# PBC-1.net
KiCad netlist of a schematic drawn in EAGLE
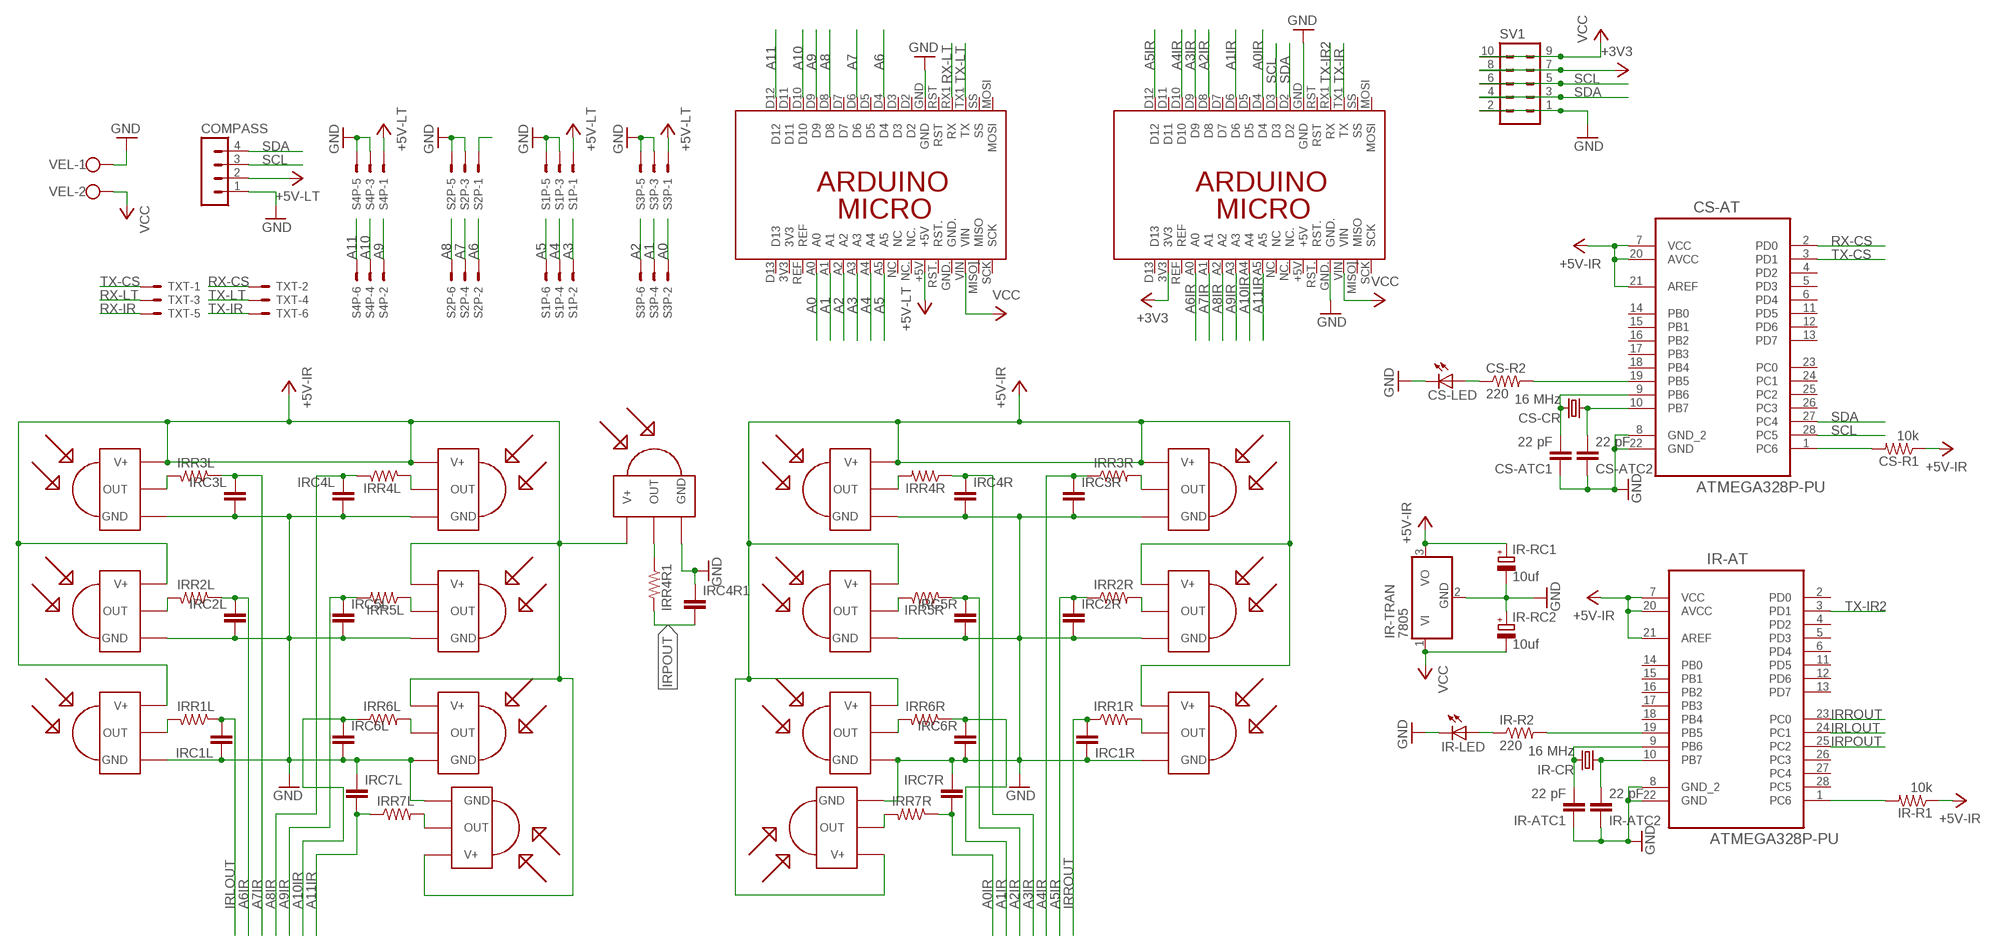
[diagram p0: schematic, sheet 1]

(export (version "E")
  (design (tool "Eeschema 10.0.6"))
  (components
    (comp (ref "COMPASS")
      (value "MA04-1")
      (footprint "eagle-import:MA04-1")
      (libsource (lib "eagle-import") (part "MA04-1"))
    )
    (comp (ref "CS-AT")
      (value "ATMEGA328P-PU")
      (footprint "eagle-import:DIP254P762X457-28")
      (libsource (lib "eagle-import") (part "ATMEGA328P-PU"))
    )
    (comp (ref "CS-ATC1")
      (value "22 pF")
      (footprint "eagle-import:C025-024X044")
      (libsource (lib "eagle-import") (part "C-EU025-024X044"))
    )
    (comp (ref "CS-ATC2")
      (value "22 pF")
      (footprint "eagle-import:C025-024X044")
      (libsource (lib "eagle-import") (part "C-EU025-024X044"))
    )
    (comp (ref "CS-CR")
      (value "16 MHz")
      (footprint "eagle-import:HC49U70")
      (libsource (lib "eagle-import") (part "CRYSTALHC49U70"))
    )
    (comp (ref "CS-LED")
      (value "LED5MM")
      (footprint "eagle-import:LED5MM")
      (libsource (lib "eagle-import") (part "LED5MM"))
    )
    (comp (ref "CS-R1")
      (value "10k")
      (footprint "eagle-import:0204_7")
      (libsource (lib "eagle-import") (part "R-US_0204/7"))
    )
    (comp (ref "CS-R2")
      (value "220")
      (footprint "eagle-import:0204_7")
      (libsource (lib "eagle-import") (part "R-US_0204/7"))
    )
    (comp (ref "IR-AT")
      (value "ATMEGA328P-PU")
      (footprint "eagle-import:DIP254P762X457-28")
      (libsource (lib "eagle-import") (part "ATMEGA328P-PU"))
    )
    (comp (ref "IR-ATC1")
      (value "22 pF")
      (footprint "eagle-import:C025-024X044")
      (libsource (lib "eagle-import") (part "C-EU025-024X044"))
    )
    (comp (ref "IR-ATC2")
      (value "22 pF")
      (footprint "eagle-import:C025-024X044")
      (libsource (lib "eagle-import") (part "C-EU025-024X044"))
    )
    (comp (ref "IR-CR")
      (value "16 MHz")
      (footprint "eagle-import:HC49U70")
      (libsource (lib "eagle-import") (part "CRYSTALHC49U70"))
    )
    (comp (ref "IR-LED")
      (value "LED5MM")
      (footprint "eagle-import:LED5MM")
      (libsource (lib "eagle-import") (part "LED5MM"))
    )
    (comp (ref "IR-R1")
      (value "10k")
      (footprint "eagle-import:0204_7")
      (libsource (lib "eagle-import") (part "R-US_0204/7"))
    )
    (comp (ref "IR-R2")
      (value "220")
      (footprint "eagle-import:0204_7")
      (libsource (lib "eagle-import") (part "R-US_0204/7"))
    )
    (comp (ref "IR-RC1")
      (value "10uf")
      (footprint "eagle-import:TT2D5")
      (libsource (lib "eagle-import") (part "CPOL-EUTT2D5"))
    )
    (comp (ref "IR-RC2")
      (value "10uf")
      (footprint "eagle-import:TT2D5")
      (libsource (lib "eagle-import") (part "CPOL-EUTT2D5"))
    )
    (comp (ref "IR-TRAN")
      (value "7805")
      (footprint "eagle-import:TO220H")
      (libsource (lib "eagle-import") (part "78T05"))
    )
    (comp (ref "IRC1L")
      (value "C-EU025-024X044")
      (footprint "eagle-import:C025-024X044")
      (libsource (lib "eagle-import") (part "C-EU025-024X044"))
    )
    (comp (ref "IRC1R")
      (value "C-EU025-024X044")
      (footprint "eagle-import:C025-024X044")
      (libsource (lib "eagle-import") (part "C-EU025-024X044"))
    )
    (comp (ref "IRC2L")
      (value "C-EU025-024X044")
      (footprint "eagle-import:C025-024X044")
      (libsource (lib "eagle-import") (part "C-EU025-024X044"))
    )
    (comp (ref "IRC2R")
      (value "C-EU025-024X044")
      (footprint "eagle-import:C025-024X044")
      (libsource (lib "eagle-import") (part "C-EU025-024X044"))
    )
    (comp (ref "IRC3L")
      (value "C-EU025-024X044")
      (footprint "eagle-import:C025-024X044")
      (libsource (lib "eagle-import") (part "C-EU025-024X044"))
    )
    (comp (ref "IRC3R")
      (value "C-EU025-024X044")
      (footprint "eagle-import:C025-024X044")
      (libsource (lib "eagle-import") (part "C-EU025-024X044"))
    )
    (comp (ref "IRC4L")
      (value "C-EU025-024X044")
      (footprint "eagle-import:C025-024X044")
      (libsource (lib "eagle-import") (part "C-EU025-024X044"))
    )
    (comp (ref "IRC4R")
      (value "C-EU025-024X044")
      (footprint "eagle-import:C025-024X044")
      (libsource (lib "eagle-import") (part "C-EU025-024X044"))
    )
    (comp (ref "IRC4R1")
      (value "C-EU025-024X044")
      (footprint "eagle-import:C025-024X044")
      (libsource (lib "eagle-import") (part "C-EU025-024X044"))
    )
    (comp (ref "IRC5L")
      (value "C-EU025-024X044")
      (footprint "eagle-import:C025-024X044")
      (libsource (lib "eagle-import") (part "C-EU025-024X044"))
    )
    (comp (ref "IRC5R")
      (value "C-EU025-024X044")
      (footprint "eagle-import:C025-024X044")
      (libsource (lib "eagle-import") (part "C-EU025-024X044"))
    )
    (comp (ref "IRC6L")
      (value "C-EU025-024X044")
      (footprint "eagle-import:C025-024X044")
      (libsource (lib "eagle-import") (part "C-EU025-024X044"))
    )
    (comp (ref "IRC6R")
      (value "C-EU025-024X044")
      (footprint "eagle-import:C025-024X044")
      (libsource (lib "eagle-import") (part "C-EU025-024X044"))
    )
    (comp (ref "IRC7L")
      (value "C-EU025-024X044")
      (footprint "eagle-import:C025-024X044")
      (libsource (lib "eagle-import") (part "C-EU025-024X044"))
    )
    (comp (ref "IRC7R")
      (value "C-EU025-024X044")
      (footprint "eagle-import:C025-024X044")
      (libsource (lib "eagle-import") (part "C-EU025-024X044"))
    )
    (comp (ref "IRD1L")
      (value "TSOP2240")
      (footprint "eagle-import:TSOP18XX")
      (libsource (lib "eagle-import") (part "TSOP1840"))
    )
    (comp (ref "IRD1R")
      (value "TSOP2240")
      (footprint "eagle-import:TSOP18XX")
      (libsource (lib "eagle-import") (part "TSOP1840"))
    )
    (comp (ref "IRD2L")
      (value "TSOP2240")
      (footprint "eagle-import:TSOP18XX")
      (libsource (lib "eagle-import") (part "TSOP1840"))
    )
    (comp (ref "IRD2R")
      (value "TSOP2240")
      (footprint "eagle-import:TSOP18XX")
      (libsource (lib "eagle-import") (part "TSOP1840"))
    )
    (comp (ref "IRD3L")
      (value "TSOP2240")
      (footprint "eagle-import:TSOP18XX")
      (libsource (lib "eagle-import") (part "TSOP1840"))
    )
    (comp (ref "IRD3R")
      (value "TSOP1840")
      (footprint "eagle-import:TSOP18XX")
      (libsource (lib "eagle-import") (part "TSOP1840"))
    )
    (comp (ref "IRD4L")
      (value "TSOP2240")
      (footprint "eagle-import:TSOP18XX")
      (libsource (lib "eagle-import") (part "TSOP1840"))
    )
    (comp (ref "IRD4R")
      (value "TSOP2240")
      (footprint "eagle-import:TSOP18XX")
      (libsource (lib "eagle-import") (part "TSOP1840"))
    )
    (comp (ref "IRD5L")
      (value "TSOP2240")
      (footprint "eagle-import:TSOP18XX")
      (libsource (lib "eagle-import") (part "TSOP1840"))
    )
    (comp (ref "IRD5R")
      (value "TSOP2240")
      (footprint "eagle-import:TSOP18XX")
      (libsource (lib "eagle-import") (part "TSOP1840"))
    )
    (comp (ref "IRD6L")
      (value "TSOP2240")
      (footprint "eagle-import:TSOP18XX")
      (libsource (lib "eagle-import") (part "TSOP1840"))
    )
    (comp (ref "IRD6R")
      (value "TSOP2240")
      (footprint "eagle-import:TSOP18XX")
      (libsource (lib "eagle-import") (part "TSOP1840"))
    )
    (comp (ref "IRD7L")
      (value "TSOP2240")
      (footprint "eagle-import:TSOP18XX")
      (libsource (lib "eagle-import") (part "TSOP1840"))
    )
    (comp (ref "IRD7R")
      (value "TSOP2240")
      (footprint "eagle-import:TSOP18XX")
      (libsource (lib "eagle-import") (part "TSOP1840"))
    )
    (comp (ref "IRDP")
      (value "TSOP2240")
      (footprint "eagle-import:TSOP18XX")
      (libsource (lib "eagle-import") (part "TSOP1840"))
    )
    (comp (ref "IRR1L")
      (value "R-US_0204/5")
      (footprint "eagle-import:0204_5")
      (libsource (lib "eagle-import") (part "R-US_0204/5"))
    )
    (comp (ref "IRR1R")
      (value "R-US_0204/5")
      (footprint "eagle-import:0204_5")
      (libsource (lib "eagle-import") (part "R-US_0204/5"))
    )
    (comp (ref "IRR2L")
      (value "R-US_0204/5")
      (footprint "eagle-import:0204_5")
      (libsource (lib "eagle-import") (part "R-US_0204/5"))
    )
    (comp (ref "IRR2R")
      (value "R-US_0204/5")
      (footprint "eagle-import:0204_5")
      (libsource (lib "eagle-import") (part "R-US_0204/5"))
    )
    (comp (ref "IRR3L")
      (value "R-US_0204/5")
      (footprint "eagle-import:0204_5")
      (libsource (lib "eagle-import") (part "R-US_0204/5"))
    )
    (comp (ref "IRR3R")
      (value "R-US_0204/5")
      (footprint "eagle-import:0204_5")
      (libsource (lib "eagle-import") (part "R-US_0204/5"))
    )
    (comp (ref "IRR4L")
      (value "R-US_0204/5")
      (footprint "eagle-import:0204_5")
      (libsource (lib "eagle-import") (part "R-US_0204/5"))
    )
    (comp (ref "IRR4R")
      (value "R-US_0204/5")
      (footprint "eagle-import:0204_5")
      (libsource (lib "eagle-import") (part "R-US_0204/5"))
    )
    (comp (ref "IRR4R1")
      (value "R-US_0204/5")
      (footprint "eagle-import:0204_5")
      (libsource (lib "eagle-import") (part "R-US_0204/5"))
    )
    (comp (ref "IRR5L")
      (value "R-US_0204/5")
      (footprint "eagle-import:0204_5")
      (libsource (lib "eagle-import") (part "R-US_0204/5"))
    )
    (comp (ref "IRR5R")
      (value "R-US_0204/5")
      (footprint "eagle-import:0204_5")
      (libsource (lib "eagle-import") (part "R-US_0204/5"))
    )
    (comp (ref "IRR6L")
      (value "R-US_0204/5")
      (footprint "eagle-import:0204_5")
      (libsource (lib "eagle-import") (part "R-US_0204/5"))
    )
    (comp (ref "IRR6R")
      (value "R-US_0204/5")
      (footprint "eagle-import:0204_5")
      (libsource (lib "eagle-import") (part "R-US_0204/5"))
    )
    (comp (ref "IRR7L")
      (value "R-US_0204/5")
      (footprint "eagle-import:0204_5")
      (libsource (lib "eagle-import") (part "R-US_0204/5"))
    )
    (comp (ref "IRR7R")
      (value "R-US_0204/5")
      (footprint "eagle-import:0204_5")
      (libsource (lib "eagle-import") (part "R-US_0204/5"))
    )
    (comp (ref "PCB1")
      (value "ARDUINO_MICRO")
      (footprint "eagle-import:ARDUINO_MICRO")
      (libsource (lib "eagle-import") (part "ARDUINO_MICRO"))
    )
    (comp (ref "PCB3")
      (value "ARDUINO_MICRO")
      (footprint "eagle-import:ARDUINO_MICRO")
      (libsource (lib "eagle-import") (part "ARDUINO_MICRO"))
    )
    (comp (ref "S1P")
      (value "332-06")
      (footprint "eagle-import:332-06")
      (libsource (lib "eagle-import") (part "332-06"))
    )
    (comp (ref "S2P")
      (value "332-06")
      (footprint "eagle-import:332-06")
      (libsource (lib "eagle-import") (part "332-06"))
    )
    (comp (ref "S3P")
      (value "332-06")
      (footprint "eagle-import:332-06")
      (libsource (lib "eagle-import") (part "332-06"))
    )
    (comp (ref "S4P")
      (value "332-06")
      (footprint "eagle-import:332-06")
      (libsource (lib "eagle-import") (part "332-06"))
    )
    (comp (ref "SV1")
      (value "MA05-2")
      (footprint "eagle-import:MA05-2")
      (libsource (lib "eagle-import") (part "MA05-2"))
    )
    (comp (ref "TXT")
      (value "87758-0616")
      (footprint "eagle-import:87758-0616")
      (libsource (lib "eagle-import") (part "87758-0616"))
    )
    (comp (ref "VEL")
      (value "W237-102")
      (footprint "eagle-import:W237-102")
      (fields (field (name "MPN") "237-102"))
      (libsource (lib "eagle-import") (part "W237-102"))
    )
  )
  (nets
    (net (code "1") (name "+3V3") (class "Default")
      (node (ref "PCB3") (pin "3V3") (pinfunction "3V3_3V3") (pintype "bidirectional"))
      (node (ref "SV1") (pin "7") (pinfunction "7_7") (pintype "passive"))
      (node (ref "SV1") (pin "8") (pinfunction "8_8") (pintype "passive"))
    )
    (net (code "2") (name "+5V-IR") (class "Default")
      (node (ref "CS-AT") (pin "20") (pinfunction "AVCC_20") (pintype "power_in"))
      (node (ref "CS-AT") (pin "21") (pinfunction "AREF_21") (pintype "input"))
      (node (ref "CS-AT") (pin "7") (pinfunction "VCC_7") (pintype "power_in"))
      (node (ref "CS-R1") (pin "1") (pinfunction "1_1") (pintype "passive"))
      (node (ref "IR-AT") (pin "20") (pinfunction "AVCC_20") (pintype "power_in"))
      (node (ref "IR-AT") (pin "21") (pinfunction "AREF_21") (pintype "input"))
      (node (ref "IR-AT") (pin "7") (pinfunction "VCC_7") (pintype "power_in"))
      (node (ref "IR-R1") (pin "1") (pinfunction "1_1") (pintype "passive"))
      (node (ref "IR-RC1") (pin "+") (pinfunction "+_+") (pintype "passive"))
      (node (ref "IR-TRAN") (pin "3") (pinfunction "VO_3") (pintype "passive"))
      (node (ref "IRD1L") (pin "VCC") (pinfunction "V+_VCC") (pintype "bidirectional"))
      (node (ref "IRD1R") (pin "VCC") (pinfunction "V+_VCC") (pintype "bidirectional"))
      (node (ref "IRD2L") (pin "VCC") (pinfunction "V+_VCC") (pintype "bidirectional"))
      (node (ref "IRD2R") (pin "VCC") (pinfunction "V+_VCC") (pintype "bidirectional"))
      (node (ref "IRD3L") (pin "VCC") (pinfunction "V+_VCC") (pintype "bidirectional"))
      (node (ref "IRD3R") (pin "VCC") (pinfunction "V+_VCC") (pintype "bidirectional"))
      (node (ref "IRD4L") (pin "VCC") (pinfunction "V+_VCC") (pintype "bidirectional"))
      (node (ref "IRD4R") (pin "VCC") (pinfunction "V+_VCC") (pintype "bidirectional"))
      (node (ref "IRD5L") (pin "VCC") (pinfunction "V+_VCC") (pintype "bidirectional"))
      (node (ref "IRD5R") (pin "VCC") (pinfunction "V+_VCC") (pintype "bidirectional"))
      (node (ref "IRD6L") (pin "VCC") (pinfunction "V+_VCC") (pintype "bidirectional"))
      (node (ref "IRD6R") (pin "VCC") (pinfunction "V+_VCC") (pintype "bidirectional"))
      (node (ref "IRD7L") (pin "VCC") (pinfunction "V+_VCC") (pintype "bidirectional"))
      (node (ref "IRD7R") (pin "VCC") (pinfunction "V+_VCC") (pintype "bidirectional"))
      (node (ref "IRDP") (pin "VCC") (pinfunction "V+_VCC") (pintype "bidirectional"))
    )
    (net (code "3") (name "+5V-LT") (class "Default")
      (node (ref "COMPASS") (pin "2") (pinfunction "2_2") (pintype "passive"))
      (node (ref "PCB1") (pin "+5V") (pinfunction "+5V_+5V") (pintype "bidirectional"))
      (node (ref "S1P") (pin "1") (pinfunction "S_1") (pintype "passive"))
      (node (ref "S3P") (pin "1") (pinfunction "S_1") (pintype "passive"))
      (node (ref "S4P") (pin "1") (pinfunction "S_1") (pintype "passive"))
    )
    (net (code "4") (name "/A0") (class "Default")
      (node (ref "PCB1") (pin "A0") (pinfunction "A0_A0") (pintype "bidirectional"))
      (node (ref "S3P") (pin "2") (pinfunction "S_2") (pintype "passive"))
    )
    (net (code "5") (name "/A0IR") (class "Default")
      (node (ref "IRC7R") (pin "2") (pinfunction "2_2") (pintype "passive"))
      (node (ref "IRR7R") (pin "1") (pinfunction "1_1") (pintype "passive"))
      (node (ref "PCB3") (pin "D4") (pinfunction "D4_D4") (pintype "bidirectional"))
    )
    (net (code "6") (name "/A1") (class "Default")
      (node (ref "PCB1") (pin "A1") (pinfunction "A1_A1") (pintype "bidirectional"))
      (node (ref "S3P") (pin "4") (pinfunction "S_4") (pintype "passive"))
    )
    (net (code "7") (name "/A1IR") (class "Default")
      (node (ref "IRC6R") (pin "1") (pinfunction "1_1") (pintype "passive"))
      (node (ref "IRR6R") (pin "1") (pinfunction "1_1") (pintype "passive"))
      (node (ref "PCB3") (pin "D6") (pinfunction "D6_D6") (pintype "bidirectional"))
    )
    (net (code "8") (name "/A2") (class "Default")
      (node (ref "PCB1") (pin "A2") (pinfunction "A2_A2") (pintype "bidirectional"))
      (node (ref "S3P") (pin "6") (pinfunction "S_6") (pintype "passive"))
    )
    (net (code "9") (name "/A2IR") (class "Default")
      (node (ref "IRC5R") (pin "1") (pinfunction "1_1") (pintype "passive"))
      (node (ref "IRR5R") (pin "2") (pinfunction "2_2") (pintype "passive"))
      (node (ref "PCB3") (pin "D8") (pinfunction "D8_D8") (pintype "bidirectional"))
    )
    (net (code "10") (name "/A3") (class "Default")
      (node (ref "PCB1") (pin "A3") (pinfunction "A3_A3") (pintype "bidirectional"))
      (node (ref "S1P") (pin "2") (pinfunction "S_2") (pintype "passive"))
    )
    (net (code "11") (name "/A3IR") (class "Default")
      (node (ref "IRC4R") (pin "1") (pinfunction "1_1") (pintype "passive"))
      (node (ref "IRR4R") (pin "1") (pinfunction "1_1") (pintype "passive"))
      (node (ref "PCB3") (pin "D9") (pinfunction "D9_D9") (pintype "bidirectional"))
    )
    (net (code "12") (name "/A4") (class "Default")
      (node (ref "PCB1") (pin "A4") (pinfunction "A4_A4") (pintype "bidirectional"))
      (node (ref "S1P") (pin "4") (pinfunction "S_4") (pintype "passive"))
    )
    (net (code "13") (name "/A4IR") (class "Default")
      (node (ref "IRC3R") (pin "1") (pinfunction "1_1") (pintype "passive"))
      (node (ref "IRR3R") (pin "1") (pinfunction "1_1") (pintype "passive"))
      (node (ref "PCB3") (pin "D10") (pinfunction "D10_D10") (pintype "bidirectional"))
    )
    (net (code "14") (name "/A5") (class "Default")
      (node (ref "PCB1") (pin "A5") (pinfunction "A5_A5") (pintype "bidirectional"))
      (node (ref "S1P") (pin "6") (pinfunction "S_6") (pintype "passive"))
    )
    (net (code "15") (name "/A5IR") (class "Default")
      (node (ref "IRC2R") (pin "1") (pinfunction "1_1") (pintype "passive"))
      (node (ref "IRR2R") (pin "1") (pinfunction "1_1") (pintype "passive"))
      (node (ref "PCB3") (pin "D12") (pinfunction "D12_D12") (pintype "bidirectional"))
    )
    (net (code "16") (name "/A6") (class "Default")
      (node (ref "PCB1") (pin "D4") (pinfunction "D4_D4") (pintype "bidirectional"))
      (node (ref "S2P") (pin "2") (pinfunction "S_2") (pintype "passive"))
    )
    (net (code "17") (name "/A6IR") (class "Default")
      (node (ref "IRC2L") (pin "1") (pinfunction "1_1") (pintype "passive"))
      (node (ref "IRR2L") (pin "1") (pinfunction "1_1") (pintype "passive"))
      (node (ref "PCB3") (pin "A0") (pinfunction "A0_A0") (pintype "bidirectional"))
    )
    (net (code "18") (name "/A7") (class "Default")
      (node (ref "PCB1") (pin "D6") (pinfunction "D6_D6") (pintype "bidirectional"))
      (node (ref "S2P") (pin "4") (pinfunction "S_4") (pintype "passive"))
    )
    (net (code "19") (name "/A7IR") (class "Default")
      (node (ref "IRC3L") (pin "1") (pinfunction "1_1") (pintype "passive"))
      (node (ref "IRR3L") (pin "1") (pinfunction "1_1") (pintype "passive"))
      (node (ref "PCB3") (pin "A1") (pinfunction "A1_A1") (pintype "bidirectional"))
    )
    (net (code "20") (name "/A8") (class "Default")
      (node (ref "PCB1") (pin "D8") (pinfunction "D8_D8") (pintype "bidirectional"))
      (node (ref "S2P") (pin "6") (pinfunction "S_6") (pintype "passive"))
    )
    (net (code "21") (name "/A8IR") (class "Default")
      (node (ref "IRC4L") (pin "1") (pinfunction "1_1") (pintype "passive"))
      (node (ref "IRR4L") (pin "1") (pinfunction "1_1") (pintype "passive"))
      (node (ref "PCB3") (pin "A2") (pinfunction "A2_A2") (pintype "bidirectional"))
    )
    (net (code "22") (name "/A9") (class "Default")
      (node (ref "PCB1") (pin "D9") (pinfunction "D9_D9") (pintype "bidirectional"))
      (node (ref "S4P") (pin "2") (pinfunction "S_2") (pintype "passive"))
    )
    (net (code "23") (name "/A9IR") (class "Default")
      (node (ref "IRC5L") (pin "1") (pinfunction "1_1") (pintype "passive"))
      (node (ref "IRR5L") (pin "2") (pinfunction "2_2") (pintype "passive"))
      (node (ref "PCB3") (pin "A3") (pinfunction "A3_A3") (pintype "bidirectional"))
    )
    (net (code "24") (name "/A10") (class "Default")
      (node (ref "PCB1") (pin "D10") (pinfunction "D10_D10") (pintype "bidirectional"))
      (node (ref "S4P") (pin "4") (pinfunction "S_4") (pintype "passive"))
    )
    (net (code "25") (name "/A10IR") (class "Default")
      (node (ref "IRC6L") (pin "1") (pinfunction "1_1") (pintype "passive"))
      (node (ref "IRR6L") (pin "1") (pinfunction "1_1") (pintype "passive"))
      (node (ref "PCB3") (pin "A4") (pinfunction "A4_A4") (pintype "bidirectional"))
    )
    (net (code "26") (name "/A11") (class "Default")
      (node (ref "PCB1") (pin "D12") (pinfunction "D12_D12") (pintype "bidirectional"))
      (node (ref "S4P") (pin "6") (pinfunction "S_6") (pintype "passive"))
    )
    (net (code "27") (name "/A11IR") (class "Default")
      (node (ref "IRC7L") (pin "2") (pinfunction "2_2") (pintype "passive"))
      (node (ref "IRR7L") (pin "1") (pinfunction "1_1") (pintype "passive"))
      (node (ref "PCB3") (pin "A5") (pinfunction "A5_A5") (pintype "bidirectional"))
    )
    (net (code "28") (name "/IRLOUT") (class "Default")
      (node (ref "IR-AT") (pin "24") (pinfunction "PC1_24") (pintype "bidirectional"))
      (node (ref "IRC1L") (pin "2") (pinfunction "2_2") (pintype "passive"))
      (node (ref "IRR1L") (pin "1") (pinfunction "1_1") (pintype "passive"))
    )
    (net (code "29") (name "/IRROUT") (class "Default")
      (node (ref "IR-AT") (pin "23") (pinfunction "PC0_23") (pintype "bidirectional"))
      (node (ref "IRC1R") (pin "2") (pinfunction "2_2") (pintype "passive"))
      (node (ref "IRR1R") (pin "1") (pinfunction "1_1") (pintype "passive"))
    )
    (net (code "30") (name "/RX-CS") (class "Default")
      (node (ref "CS-AT") (pin "2") (pinfunction "PD0_2") (pintype "bidirectional"))
      (node (ref "TXT") (pin "2") (pinfunction "S_2") (pintype "passive"))
    )
    (net (code "31") (name "/RX-IR") (class "Default")
      (node (ref "TXT") (pin "5") (pinfunction "S_5") (pintype "passive"))
    )
    (net (code "32") (name "/RX-LT") (class "Default")
      (node (ref "PCB1") (pin "RX1") (pinfunction "RX_RX1") (pintype "bidirectional"))
      (node (ref "TXT") (pin "3") (pinfunction "S_3") (pintype "passive"))
    )
    (net (code "33") (name "/SCL") (class "Default")
      (node (ref "COMPASS") (pin "3") (pinfunction "3_3") (pintype "passive"))
      (node (ref "CS-AT") (pin "28") (pinfunction "PC5_28") (pintype "bidirectional"))
      (node (ref "PCB3") (pin "D3") (pinfunction "D3_D3") (pintype "bidirectional"))
      (node (ref "SV1") (pin "5") (pinfunction "5_5") (pintype "passive"))
      (node (ref "SV1") (pin "6") (pinfunction "6_6") (pintype "passive"))
    )
    (net (code "34") (name "/SDA") (class "Default")
      (node (ref "COMPASS") (pin "4") (pinfunction "4_4") (pintype "passive"))
      (node (ref "CS-AT") (pin "27") (pinfunction "PC4_27") (pintype "bidirectional"))
      (node (ref "PCB3") (pin "D2") (pinfunction "D2_D2") (pintype "bidirectional"))
      (node (ref "SV1") (pin "3") (pinfunction "3_3") (pintype "passive"))
      (node (ref "SV1") (pin "4") (pinfunction "4_4") (pintype "passive"))
    )
    (net (code "35") (name "/TX-CS") (class "Default")
      (node (ref "CS-AT") (pin "3") (pinfunction "PD1_3") (pintype "bidirectional"))
      (node (ref "TXT") (pin "1") (pinfunction "S_1") (pintype "passive"))
    )
    (net (code "36") (name "/TX-IR") (class "Default")
      (node (ref "PCB3") (pin "TX1") (pinfunction "TX_TX1") (pintype "bidirectional"))
      (node (ref "TXT") (pin "6") (pinfunction "S_6") (pintype "passive"))
    )
    (net (code "37") (name "/TX-IR2") (class "Default")
      (node (ref "IR-AT") (pin "3") (pinfunction "PD1_3") (pintype "bidirectional"))
      (node (ref "PCB3") (pin "RX1") (pinfunction "RX_RX1") (pintype "bidirectional"))
    )
    (net (code "38") (name "/TX-LT") (class "Default")
      (node (ref "PCB1") (pin "TX1") (pinfunction "TX_TX1") (pintype "bidirectional"))
      (node (ref "TXT") (pin "4") (pinfunction "S_4") (pintype "passive"))
    )
    (net (code "39") (name "GND") (class "Default")
      (node (ref "COMPASS") (pin "1") (pinfunction "1_1") (pintype "passive"))
      (node (ref "CS-AT") (pin "22") (pinfunction "GND_22") (pintype "passive"))
      (node (ref "CS-AT") (pin "8") (pinfunction "GND_2_8") (pintype "passive"))
      (node (ref "CS-ATC1") (pin "1") (pinfunction "1_1") (pintype "passive"))
      (node (ref "CS-ATC2") (pin "1") (pinfunction "1_1") (pintype "passive"))
      (node (ref "CS-LED") (pin "K") (pinfunction "C_K") (pintype "passive"))
      (node (ref "IR-AT") (pin "22") (pinfunction "GND_22") (pintype "passive"))
      (node (ref "IR-AT") (pin "8") (pinfunction "GND_2_8") (pintype "passive"))
      (node (ref "IR-ATC1") (pin "1") (pinfunction "1_1") (pintype "passive"))
      (node (ref "IR-ATC2") (pin "1") (pinfunction "1_1") (pintype "passive"))
      (node (ref "IR-LED") (pin "K") (pinfunction "C_K") (pintype "passive"))
      (node (ref "IR-RC1") (pin "-") (pinfunction "-_-") (pintype "passive"))
      (node (ref "IR-RC2") (pin "+") (pinfunction "+_+") (pintype "passive"))
      (node (ref "IR-TRAN") (pin "2") (pinfunction "GND_2") (pintype "passive"))
      (node (ref "IRC1L") (pin "1") (pinfunction "1_1") (pintype "passive"))
      (node (ref "IRC1R") (pin "1") (pinfunction "1_1") (pintype "passive"))
      (node (ref "IRC2L") (pin "2") (pinfunction "2_2") (pintype "passive"))
      (node (ref "IRC2R") (pin "2") (pinfunction "2_2") (pintype "passive"))
      (node (ref "IRC3L") (pin "2") (pinfunction "2_2") (pintype "passive"))
      (node (ref "IRC3R") (pin "2") (pinfunction "2_2") (pintype "passive"))
      (node (ref "IRC4L") (pin "2") (pinfunction "2_2") (pintype "passive"))
      (node (ref "IRC4R") (pin "2") (pinfunction "2_2") (pintype "passive"))
      (node (ref "IRC4R1") (pin "1") (pinfunction "1_1") (pintype "passive"))
      (node (ref "IRC5L") (pin "2") (pinfunction "2_2") (pintype "passive"))
      (node (ref "IRC5R") (pin "2") (pinfunction "2_2") (pintype "passive"))
      (node (ref "IRC6L") (pin "2") (pinfunction "2_2") (pintype "passive"))
      (node (ref "IRC6R") (pin "2") (pinfunction "2_2") (pintype "passive"))
      (node (ref "IRC7L") (pin "1") (pinfunction "1_1") (pintype "passive"))
      (node (ref "IRC7R") (pin "1") (pinfunction "1_1") (pintype "passive"))
      (node (ref "IRD1L") (pin "GND") (pinfunction "GND_GND") (pintype "bidirectional"))
      (node (ref "IRD1R") (pin "GND") (pinfunction "GND_GND") (pintype "bidirectional"))
      (node (ref "IRD2L") (pin "GND") (pinfunction "GND_GND") (pintype "bidirectional"))
      (node (ref "IRD2R") (pin "GND") (pinfunction "GND_GND") (pintype "bidirectional"))
      (node (ref "IRD3L") (pin "GND") (pinfunction "GND_GND") (pintype "bidirectional"))
      (node (ref "IRD3R") (pin "GND") (pinfunction "GND_GND") (pintype "bidirectional"))
      (node (ref "IRD4L") (pin "GND") (pinfunction "GND_GND") (pintype "bidirectional"))
      (node (ref "IRD4R") (pin "GND") (pinfunction "GND_GND") (pintype "bidirectional"))
      (node (ref "IRD5L") (pin "GND") (pinfunction "GND_GND") (pintype "bidirectional"))
      (node (ref "IRD5R") (pin "GND") (pinfunction "GND_GND") (pintype "bidirectional"))
      (node (ref "IRD6L") (pin "GND") (pinfunction "GND_GND") (pintype "bidirectional"))
      (node (ref "IRD6R") (pin "GND") (pinfunction "GND_GND") (pintype "bidirectional"))
      (node (ref "IRD7L") (pin "GND") (pinfunction "GND_GND") (pintype "bidirectional"))
      (node (ref "IRD7R") (pin "GND") (pinfunction "GND_GND") (pintype "bidirectional"))
      (node (ref "IRDP") (pin "GND") (pinfunction "GND_GND") (pintype "bidirectional"))
      (node (ref "PCB1") (pin "GND") (pinfunction "GND_GND") (pintype "bidirectional"))
      (node (ref "PCB3") (pin "GND") (pinfunction "GND_GND") (pintype "bidirectional"))
      (node (ref "PCB3") (pin "GND.") (pinfunction "GND._GND.") (pintype "bidirectional"))
      (node (ref "S1P") (pin "3") (pinfunction "S_3") (pintype "passive"))
      (node (ref "S1P") (pin "5") (pinfunction "S_5") (pintype "passive"))
      (node (ref "S2P") (pin "3") (pinfunction "S_3") (pintype "passive"))
      (node (ref "S2P") (pin "5") (pinfunction "S_5") (pintype "passive"))
      (node (ref "S3P") (pin "3") (pinfunction "S_3") (pintype "passive"))
      (node (ref "S3P") (pin "5") (pinfunction "S_5") (pintype "passive"))
      (node (ref "S4P") (pin "3") (pinfunction "S_3") (pintype "passive"))
      (node (ref "S4P") (pin "5") (pinfunction "S_5") (pintype "passive"))
      (node (ref "SV1") (pin "1") (pinfunction "1_1") (pintype "passive"))
      (node (ref "SV1") (pin "2") (pinfunction "2_2") (pintype "passive"))
      (node (ref "VEL") (pin "1") (pinfunction "KL_1") (pintype "passive"))
    )
    (net (code "40") (name "IRPOUT") (class "Default")
      (node (ref "IR-AT") (pin "25") (pinfunction "PC2_25") (pintype "bidirectional"))
      (node (ref "IRC4R1") (pin "2") (pinfunction "2_2") (pintype "passive"))
      (node (ref "IRR4R1") (pin "2") (pinfunction "2_2") (pintype "passive"))
    )
    (net (code "41") (name "Net-(CS-AT-PB5)") (class "Default")
      (node (ref "CS-AT") (pin "19") (pinfunction "PB5_19") (pintype "bidirectional"))
      (node (ref "CS-R2") (pin "2") (pinfunction "2_2") (pintype "passive"))
    )
    (net (code "42") (name "Net-(CS-AT-PB6)") (class "Default")
      (node (ref "CS-AT") (pin "9") (pinfunction "PB6_9") (pintype "bidirectional"))
      (node (ref "CS-ATC1") (pin "2") (pinfunction "2_2") (pintype "passive"))
      (node (ref "CS-CR") (pin "2") (pinfunction "2_2") (pintype "passive"))
    )
    (net (code "43") (name "Net-(CS-AT-PB7)") (class "Default")
      (node (ref "CS-AT") (pin "10") (pinfunction "PB7_10") (pintype "bidirectional"))
      (node (ref "CS-ATC2") (pin "2") (pinfunction "2_2") (pintype "passive"))
      (node (ref "CS-CR") (pin "1") (pinfunction "1_1") (pintype "passive"))
    )
    (net (code "44") (name "Net-(CS-AT-PC6)") (class "Default")
      (node (ref "CS-AT") (pin "1") (pinfunction "PC6_1") (pintype "bidirectional"))
      (node (ref "CS-R1") (pin "2") (pinfunction "2_2") (pintype "passive"))
    )
    (net (code "45") (name "Net-(CS-LED-PadA)") (class "Default")
      (node (ref "CS-LED") (pin "A") (pinfunction "A_A") (pintype "passive"))
      (node (ref "CS-R2") (pin "1") (pinfunction "1_1") (pintype "passive"))
    )
    (net (code "46") (name "Net-(IR-AT-PB5)") (class "Default")
      (node (ref "IR-AT") (pin "19") (pinfunction "PB5_19") (pintype "bidirectional"))
      (node (ref "IR-R2") (pin "2") (pinfunction "2_2") (pintype "passive"))
    )
    (net (code "47") (name "Net-(IR-AT-PB6)") (class "Default")
      (node (ref "IR-AT") (pin "9") (pinfunction "PB6_9") (pintype "bidirectional"))
      (node (ref "IR-ATC1") (pin "2") (pinfunction "2_2") (pintype "passive"))
      (node (ref "IR-CR") (pin "2") (pinfunction "2_2") (pintype "passive"))
    )
    (net (code "48") (name "Net-(IR-AT-PB7)") (class "Default")
      (node (ref "IR-AT") (pin "10") (pinfunction "PB7_10") (pintype "bidirectional"))
      (node (ref "IR-ATC2") (pin "2") (pinfunction "2_2") (pintype "passive"))
      (node (ref "IR-CR") (pin "1") (pinfunction "1_1") (pintype "passive"))
    )
    (net (code "49") (name "Net-(IR-AT-PC6)") (class "Default")
      (node (ref "IR-AT") (pin "1") (pinfunction "PC6_1") (pintype "bidirectional"))
      (node (ref "IR-R1") (pin "2") (pinfunction "2_2") (pintype "passive"))
    )
    (net (code "50") (name "Net-(IR-LED-PadA)") (class "Default")
      (node (ref "IR-LED") (pin "A") (pinfunction "A_A") (pintype "passive"))
      (node (ref "IR-R2") (pin "1") (pinfunction "1_1") (pintype "passive"))
    )
    (net (code "51") (name "Net-(IRD1L-PadOUT)") (class "Default")
      (node (ref "IRD1L") (pin "OUT") (pinfunction "OUT_OUT") (pintype "bidirectional"))
      (node (ref "IRR1L") (pin "2") (pinfunction "2_2") (pintype "passive"))
    )
    (net (code "52") (name "Net-(IRD1R-PadOUT)") (class "Default")
      (node (ref "IRD1R") (pin "OUT") (pinfunction "OUT_OUT") (pintype "bidirectional"))
      (node (ref "IRR1R") (pin "2") (pinfunction "2_2") (pintype "passive"))
    )
    (net (code "53") (name "Net-(IRD2L-PadOUT)") (class "Default")
      (node (ref "IRD2L") (pin "OUT") (pinfunction "OUT_OUT") (pintype "bidirectional"))
      (node (ref "IRR2L") (pin "2") (pinfunction "2_2") (pintype "passive"))
    )
    (net (code "54") (name "Net-(IRD2R-PadOUT)") (class "Default")
      (node (ref "IRD2R") (pin "OUT") (pinfunction "OUT_OUT") (pintype "bidirectional"))
      (node (ref "IRR2R") (pin "2") (pinfunction "2_2") (pintype "passive"))
    )
    (net (code "55") (name "Net-(IRD3L-PadOUT)") (class "Default")
      (node (ref "IRD3L") (pin "OUT") (pinfunction "OUT_OUT") (pintype "bidirectional"))
      (node (ref "IRR3L") (pin "2") (pinfunction "2_2") (pintype "passive"))
    )
    (net (code "56") (name "Net-(IRD3R-PadOUT)") (class "Default")
      (node (ref "IRD3R") (pin "OUT") (pinfunction "OUT_OUT") (pintype "bidirectional"))
      (node (ref "IRR3R") (pin "2") (pinfunction "2_2") (pintype "passive"))
    )
    (net (code "57") (name "Net-(IRD4L-PadOUT)") (class "Default")
      (node (ref "IRD4L") (pin "OUT") (pinfunction "OUT_OUT") (pintype "bidirectional"))
      (node (ref "IRR4L") (pin "2") (pinfunction "2_2") (pintype "passive"))
    )
    (net (code "58") (name "Net-(IRD4R-PadOUT)") (class "Default")
      (node (ref "IRD4R") (pin "OUT") (pinfunction "OUT_OUT") (pintype "bidirectional"))
      (node (ref "IRR4R") (pin "2") (pinfunction "2_2") (pintype "passive"))
    )
    (net (code "59") (name "Net-(IRD5L-PadOUT)") (class "Default")
      (node (ref "IRD5L") (pin "OUT") (pinfunction "OUT_OUT") (pintype "bidirectional"))
      (node (ref "IRR5L") (pin "1") (pinfunction "1_1") (pintype "passive"))
    )
    (net (code "60") (name "Net-(IRD5R-PadOUT)") (class "Default")
      (node (ref "IRD5R") (pin "OUT") (pinfunction "OUT_OUT") (pintype "bidirectional"))
      (node (ref "IRR5R") (pin "1") (pinfunction "1_1") (pintype "passive"))
    )
    (net (code "61") (name "Net-(IRD6L-PadOUT)") (class "Default")
      (node (ref "IRD6L") (pin "OUT") (pinfunction "OUT_OUT") (pintype "bidirectional"))
      (node (ref "IRR6L") (pin "2") (pinfunction "2_2") (pintype "passive"))
    )
    (net (code "62") (name "Net-(IRD6R-PadOUT)") (class "Default")
      (node (ref "IRD6R") (pin "OUT") (pinfunction "OUT_OUT") (pintype "bidirectional"))
      (node (ref "IRR6R") (pin "2") (pinfunction "2_2") (pintype "passive"))
    )
    (net (code "63") (name "Net-(IRD7L-PadOUT)") (class "Default")
      (node (ref "IRD7L") (pin "OUT") (pinfunction "OUT_OUT") (pintype "bidirectional"))
      (node (ref "IRR7L") (pin "2") (pinfunction "2_2") (pintype "passive"))
    )
    (net (code "64") (name "Net-(IRD7R-PadOUT)") (class "Default")
      (node (ref "IRD7R") (pin "OUT") (pinfunction "OUT_OUT") (pintype "bidirectional"))
      (node (ref "IRR7R") (pin "2") (pinfunction "2_2") (pintype "passive"))
    )
    (net (code "65") (name "Net-(IRDP-PadOUT)") (class "Default")
      (node (ref "IRDP") (pin "OUT") (pinfunction "OUT_OUT") (pintype "bidirectional"))
      (node (ref "IRR4R1") (pin "1") (pinfunction "1_1") (pintype "passive"))
    )
    (net (code "66") (name "VCC") (class "Default")
      (node (ref "IR-RC2") (pin "-") (pinfunction "-_-") (pintype "passive"))
      (node (ref "IR-TRAN") (pin "1") (pinfunction "VI_1") (pintype "input"))
      (node (ref "PCB1") (pin "VIN") (pinfunction "VIN_VIN") (pintype "bidirectional"))
      (node (ref "PCB3") (pin "VIN") (pinfunction "VIN_VIN") (pintype "bidirectional"))
      (node (ref "SV1") (pin "10") (pinfunction "10_10") (pintype "passive"))
      (node (ref "SV1") (pin "9") (pinfunction "9_9") (pintype "passive"))
      (node (ref "VEL") (pin "2") (pinfunction "KL_2") (pintype "passive"))
    )
    (net (code "67") (name "unconnected-(CS-AT-PB0-Pad14)") (class "Default")
      (node (ref "CS-AT") (pin "14") (pinfunction "PB0_14") (pintype "bidirectional"))
    )
    (net (code "68") (name "unconnected-(CS-AT-PB1-Pad15)") (class "Default")
      (node (ref "CS-AT") (pin "15") (pinfunction "PB1_15") (pintype "bidirectional"))
    )
    (net (code "69") (name "unconnected-(CS-AT-PB2-Pad16)") (class "Default")
      (node (ref "CS-AT") (pin "16") (pinfunction "PB2_16") (pintype "bidirectional"))
    )
    (net (code "70") (name "unconnected-(CS-AT-PB3-Pad17)") (class "Default")
      (node (ref "CS-AT") (pin "17") (pinfunction "PB3_17") (pintype "bidirectional"))
    )
    (net (code "71") (name "unconnected-(CS-AT-PB4-Pad18)") (class "Default")
      (node (ref "CS-AT") (pin "18") (pinfunction "PB4_18") (pintype "bidirectional"))
    )
    (net (code "72") (name "unconnected-(CS-AT-PC0-Pad23)") (class "Default")
      (node (ref "CS-AT") (pin "23") (pinfunction "PC0_23") (pintype "bidirectional"))
    )
    (net (code "73") (name "unconnected-(CS-AT-PC1-Pad24)") (class "Default")
      (node (ref "CS-AT") (pin "24") (pinfunction "PC1_24") (pintype "bidirectional"))
    )
    (net (code "74") (name "unconnected-(CS-AT-PC2-Pad25)") (class "Default")
      (node (ref "CS-AT") (pin "25") (pinfunction "PC2_25") (pintype "bidirectional"))
    )
    (net (code "75") (name "unconnected-(CS-AT-PC3-Pad26)") (class "Default")
      (node (ref "CS-AT") (pin "26") (pinfunction "PC3_26") (pintype "bidirectional"))
    )
    (net (code "76") (name "unconnected-(CS-AT-PD2-Pad4)") (class "Default")
      (node (ref "CS-AT") (pin "4") (pinfunction "PD2_4") (pintype "bidirectional"))
    )
    (net (code "77") (name "unconnected-(CS-AT-PD3-Pad5)") (class "Default")
      (node (ref "CS-AT") (pin "5") (pinfunction "PD3_5") (pintype "bidirectional"))
    )
    (net (code "78") (name "unconnected-(CS-AT-PD4-Pad6)") (class "Default")
      (node (ref "CS-AT") (pin "6") (pinfunction "PD4_6") (pintype "bidirectional"))
    )
    (net (code "79") (name "unconnected-(CS-AT-PD5-Pad11)") (class "Default")
      (node (ref "CS-AT") (pin "11") (pinfunction "PD5_11") (pintype "bidirectional"))
    )
    (net (code "80") (name "unconnected-(CS-AT-PD6-Pad12)") (class "Default")
      (node (ref "CS-AT") (pin "12") (pinfunction "PD6_12") (pintype "bidirectional"))
    )
    (net (code "81") (name "unconnected-(CS-AT-PD7-Pad13)") (class "Default")
      (node (ref "CS-AT") (pin "13") (pinfunction "PD7_13") (pintype "bidirectional"))
    )
    (net (code "82") (name "unconnected-(IR-AT-PB0-Pad14)") (class "Default")
      (node (ref "IR-AT") (pin "14") (pinfunction "PB0_14") (pintype "bidirectional"))
    )
    (net (code "83") (name "unconnected-(IR-AT-PB1-Pad15)") (class "Default")
      (node (ref "IR-AT") (pin "15") (pinfunction "PB1_15") (pintype "bidirectional"))
    )
    (net (code "84") (name "unconnected-(IR-AT-PB2-Pad16)") (class "Default")
      (node (ref "IR-AT") (pin "16") (pinfunction "PB2_16") (pintype "bidirectional"))
    )
    (net (code "85") (name "unconnected-(IR-AT-PB3-Pad17)") (class "Default")
      (node (ref "IR-AT") (pin "17") (pinfunction "PB3_17") (pintype "bidirectional"))
    )
    (net (code "86") (name "unconnected-(IR-AT-PB4-Pad18)") (class "Default")
      (node (ref "IR-AT") (pin "18") (pinfunction "PB4_18") (pintype "bidirectional"))
    )
    (net (code "87") (name "unconnected-(IR-AT-PC3-Pad26)") (class "Default")
      (node (ref "IR-AT") (pin "26") (pinfunction "PC3_26") (pintype "bidirectional"))
    )
    (net (code "88") (name "unconnected-(IR-AT-PC4-Pad27)") (class "Default")
      (node (ref "IR-AT") (pin "27") (pinfunction "PC4_27") (pintype "bidirectional"))
    )
    (net (code "89") (name "unconnected-(IR-AT-PC5-Pad28)") (class "Default")
      (node (ref "IR-AT") (pin "28") (pinfunction "PC5_28") (pintype "bidirectional"))
    )
    (net (code "90") (name "unconnected-(IR-AT-PD0-Pad2)") (class "Default")
      (node (ref "IR-AT") (pin "2") (pinfunction "PD0_2") (pintype "bidirectional"))
    )
    (net (code "91") (name "unconnected-(IR-AT-PD2-Pad4)") (class "Default")
      (node (ref "IR-AT") (pin "4") (pinfunction "PD2_4") (pintype "bidirectional"))
    )
    (net (code "92") (name "unconnected-(IR-AT-PD3-Pad5)") (class "Default")
      (node (ref "IR-AT") (pin "5") (pinfunction "PD3_5") (pintype "bidirectional"))
    )
    (net (code "93") (name "unconnected-(IR-AT-PD4-Pad6)") (class "Default")
      (node (ref "IR-AT") (pin "6") (pinfunction "PD4_6") (pintype "bidirectional"))
    )
    (net (code "94") (name "unconnected-(IR-AT-PD5-Pad11)") (class "Default")
      (node (ref "IR-AT") (pin "11") (pinfunction "PD5_11") (pintype "bidirectional"))
    )
    (net (code "95") (name "unconnected-(IR-AT-PD6-Pad12)") (class "Default")
      (node (ref "IR-AT") (pin "12") (pinfunction "PD6_12") (pintype "bidirectional"))
    )
    (net (code "96") (name "unconnected-(IR-AT-PD7-Pad13)") (class "Default")
      (node (ref "IR-AT") (pin "13") (pinfunction "PD7_13") (pintype "bidirectional"))
    )
    (net (code "97") (name "unconnected-(PCB1-MISO-PadMISO])") (class "Default")
      (node (ref "PCB1") (pin "MISO]") (pinfunction "MISO_MISO]") (pintype "bidirectional"))
    )
    (net (code "98") (name "unconnected-(PCB1-Pad3V3)") (class "Default")
      (node (ref "PCB1") (pin "3V3") (pinfunction "3V3_3V3") (pintype "bidirectional"))
    )
    (net (code "99") (name "unconnected-(PCB1-PadD2)") (class "Default")
      (node (ref "PCB1") (pin "D2") (pinfunction "D2_D2") (pintype "bidirectional"))
    )
    (net (code "100") (name "unconnected-(PCB1-PadD3)") (class "Default")
      (node (ref "PCB1") (pin "D3") (pinfunction "D3_D3") (pintype "bidirectional"))
    )
    (net (code "101") (name "unconnected-(PCB1-PadD5)") (class "Default")
      (node (ref "PCB1") (pin "D5") (pinfunction "D5_D5") (pintype "bidirectional"))
    )
    (net (code "102") (name "unconnected-(PCB1-PadD7)") (class "Default")
      (node (ref "PCB1") (pin "D7") (pinfunction "D7_D7") (pintype "bidirectional"))
    )
    (net (code "103") (name "unconnected-(PCB1-PadD11)") (class "Default")
      (node (ref "PCB1") (pin "D11") (pinfunction "D11_D11") (pintype "bidirectional"))
    )
    (net (code "104") (name "unconnected-(PCB1-PadD13)") (class "Default")
      (node (ref "PCB1") (pin "D13") (pinfunction "D13_D13") (pintype "bidirectional"))
    )
    (net (code "105") (name "unconnected-(PCB1-PadGND.)") (class "Default")
      (node (ref "PCB1") (pin "GND.") (pinfunction "GND._GND.") (pintype "bidirectional"))
    )
    (net (code "106") (name "unconnected-(PCB1-PadMOSI)") (class "Default")
      (node (ref "PCB1") (pin "MOSI") (pinfunction "MOSI_MOSI") (pintype "bidirectional"))
    )
    (net (code "107") (name "unconnected-(PCB1-PadNC)") (class "Default")
      (node (ref "PCB1") (pin "NC") (pinfunction "NC_NC") (pintype "bidirectional"))
    )
    (net (code "108") (name "unconnected-(PCB1-PadNC.)") (class "Default")
      (node (ref "PCB1") (pin "NC.") (pinfunction "NC._NC.") (pintype "bidirectional"))
    )
    (net (code "109") (name "unconnected-(PCB1-PadREF)") (class "Default")
      (node (ref "PCB1") (pin "REF") (pinfunction "REF_REF") (pintype "bidirectional"))
    )
    (net (code "110") (name "unconnected-(PCB1-PadRST)") (class "Default")
      (node (ref "PCB1") (pin "RST") (pinfunction "RST_RST") (pintype "bidirectional"))
    )
    (net (code "111") (name "unconnected-(PCB1-PadRST.)") (class "Default")
      (node (ref "PCB1") (pin "RST.") (pinfunction "RST._RST.") (pintype "bidirectional"))
    )
    (net (code "112") (name "unconnected-(PCB1-PadSCK)") (class "Default")
      (node (ref "PCB1") (pin "SCK") (pinfunction "SCK_SCK") (pintype "bidirectional"))
    )
    (net (code "113") (name "unconnected-(PCB1-PadSS)") (class "Default")
      (node (ref "PCB1") (pin "SS") (pinfunction "SS_SS") (pintype "bidirectional"))
    )
    (net (code "114") (name "unconnected-(PCB3-MISO-PadMISO])") (class "Default")
      (node (ref "PCB3") (pin "MISO]") (pinfunction "MISO_MISO]") (pintype "bidirectional"))
    )
    (net (code "115") (name "unconnected-(PCB3-Pad+5V)") (class "Default")
      (node (ref "PCB3") (pin "+5V") (pinfunction "+5V_+5V") (pintype "bidirectional"))
    )
    (net (code "116") (name "unconnected-(PCB3-PadD5)") (class "Default")
      (node (ref "PCB3") (pin "D5") (pinfunction "D5_D5") (pintype "bidirectional"))
    )
    (net (code "117") (name "unconnected-(PCB3-PadD7)") (class "Default")
      (node (ref "PCB3") (pin "D7") (pinfunction "D7_D7") (pintype "bidirectional"))
    )
    (net (code "118") (name "unconnected-(PCB3-PadD11)") (class "Default")
      (node (ref "PCB3") (pin "D11") (pinfunction "D11_D11") (pintype "bidirectional"))
    )
    (net (code "119") (name "unconnected-(PCB3-PadD13)") (class "Default")
      (node (ref "PCB3") (pin "D13") (pinfunction "D13_D13") (pintype "bidirectional"))
    )
    (net (code "120") (name "unconnected-(PCB3-PadMOSI)") (class "Default")
      (node (ref "PCB3") (pin "MOSI") (pinfunction "MOSI_MOSI") (pintype "bidirectional"))
    )
    (net (code "121") (name "unconnected-(PCB3-PadNC)") (class "Default")
      (node (ref "PCB3") (pin "NC") (pinfunction "NC_NC") (pintype "bidirectional"))
    )
    (net (code "122") (name "unconnected-(PCB3-PadNC.)") (class "Default")
      (node (ref "PCB3") (pin "NC.") (pinfunction "NC._NC.") (pintype "bidirectional"))
    )
    (net (code "123") (name "unconnected-(PCB3-PadREF)") (class "Default")
      (node (ref "PCB3") (pin "REF") (pinfunction "REF_REF") (pintype "bidirectional"))
    )
    (net (code "124") (name "unconnected-(PCB3-PadRST)") (class "Default")
      (node (ref "PCB3") (pin "RST") (pinfunction "RST_RST") (pintype "bidirectional"))
    )
    (net (code "125") (name "unconnected-(PCB3-PadRST.)") (class "Default")
      (node (ref "PCB3") (pin "RST.") (pinfunction "RST._RST.") (pintype "bidirectional"))
    )
    (net (code "126") (name "unconnected-(PCB3-PadSCK)") (class "Default")
      (node (ref "PCB3") (pin "SCK") (pinfunction "SCK_SCK") (pintype "bidirectional"))
    )
    (net (code "127") (name "unconnected-(PCB3-PadSS)") (class "Default")
      (node (ref "PCB3") (pin "SS") (pinfunction "SS_SS") (pintype "bidirectional"))
    )
    (net (code "128") (name "unconnected-(S2PA-S-Pad1)") (class "Default")
      (node (ref "S2P") (pin "1") (pinfunction "S_1") (pintype "passive"))
    )
  )
)
